# untitled.net
KiCad netlist of a schematic drawn in EAGLE
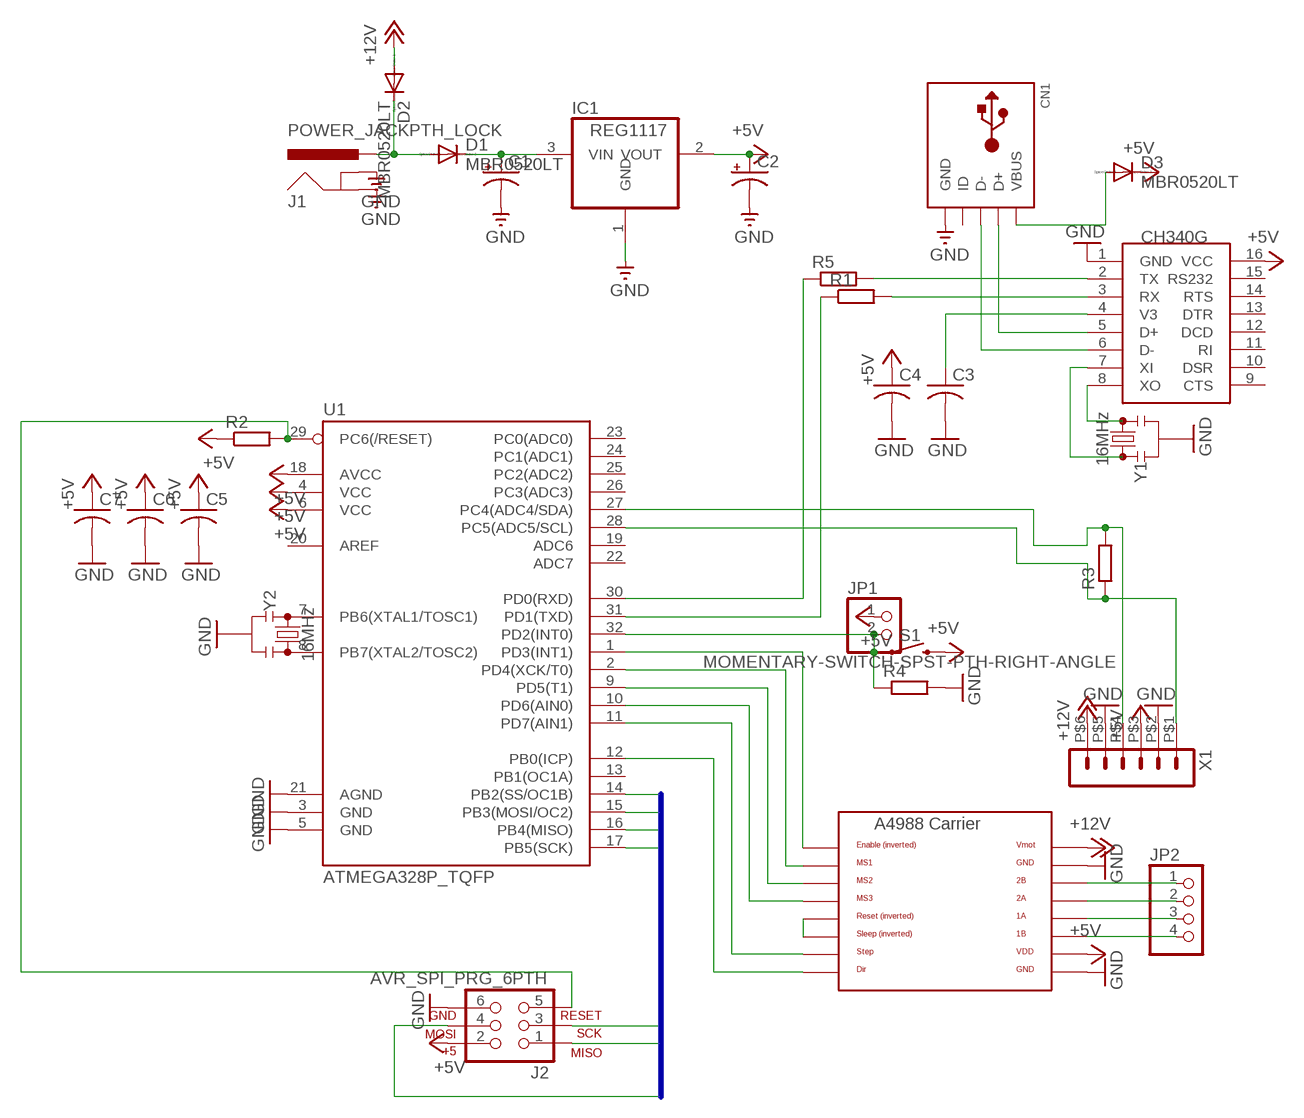
[diagram p0: schematic, sheet 1]

(export (version "E")
  (design (tool "Eeschema 10.0.6"))
  (components
    (comp (ref "C1")
      (value "CPOL-US153CLV-0405")
      (footprint "eagle-import:153CLV-0405")
      (libsource (lib "eagle-import") (part "CPOL-US153CLV-0405"))
    )
    (comp (ref "C2")
      (value "CPOL-US153CLV-0405")
      (footprint "eagle-import:153CLV-0405")
      (libsource (lib "eagle-import") (part "CPOL-US153CLV-0405"))
    )
    (comp (ref "C3")
      (value "C-USC1210")
      (footprint "eagle-import:C1210")
      (libsource (lib "eagle-import") (part "C-USC1210"))
    )
    (comp (ref "C4")
      (value "C-USC1210")
      (footprint "eagle-import:C1210")
      (libsource (lib "eagle-import") (part "C-USC1210"))
    )
    (comp (ref "C5")
      (value "C-USC1210")
      (footprint "eagle-import:C1210")
      (libsource (lib "eagle-import") (part "C-USC1210"))
    )
    (comp (ref "C6")
      (value "C-USC1210")
      (footprint "eagle-import:C1210")
      (libsource (lib "eagle-import") (part "C-USC1210"))
    )
    (comp (ref "C7")
      (value "C-USC1210")
      (footprint "eagle-import:C1210")
      (libsource (lib "eagle-import") (part "C-USC1210"))
    )
    (comp (ref "CN1")
      (value "USBMINIB")
      (footprint "eagle-import:USB-MINIB")
      (libsource (lib "eagle-import") (part "USBMINIB"))
    )
    (comp (ref "D1")
      (value "MBR0520LT")
      (footprint "eagle-import:SOD123")
      (libsource (lib "eagle-import") (part "MBR0520LT"))
    )
    (comp (ref "D2")
      (value "MBR0520LT")
      (footprint "eagle-import:SOD123")
      (libsource (lib "eagle-import") (part "MBR0520LT"))
    )
    (comp (ref "D3")
      (value "MBR0520LT")
      (footprint "eagle-import:SOD123")
      (libsource (lib "eagle-import") (part "MBR0520LT"))
    )
    (comp (ref "IC1")
      (value "REG1117")
      (footprint "eagle-import:SOT223")
      (libsource (lib "eagle-import") (part "REG1117"))
    )
    (comp (ref "J1")
      (value "POWER_JACKPTH_LOCK")
      (footprint "eagle-import:POWER_JACK_PTH_LOCK")
      (libsource (lib "eagle-import") (part "POWER_JACKPTH_LOCK"))
    )
    (comp (ref "J2")
      (value "AVR_SPI_PRG_6PTH")
      (footprint "eagle-import:2X3")
      (libsource (lib "eagle-import") (part "AVR_SPI_PRG_6PTH"))
    )
    (comp (ref "JP1")
      (value "PINHD-1X2")
      (footprint "eagle-import:1X02")
      (libsource (lib "eagle-import") (part "PINHD-1X2"))
    )
    (comp (ref "JP2")
      (value "PINHD-1X4")
      (footprint "eagle-import:1X04")
      (libsource (lib "eagle-import") (part "PINHD-1X4"))
    )
    (comp (ref "R1")
      (value "R-EU_MELF0207W")
      (footprint "eagle-import:MINI_MELF-0207W")
      (libsource (lib "eagle-import") (part "R-EU_MELF0207W"))
    )
    (comp (ref "R2")
      (value "R-EU_MELF0207W")
      (footprint "eagle-import:MINI_MELF-0207W")
      (libsource (lib "eagle-import") (part "R-EU_MELF0207W"))
    )
    (comp (ref "R3")
      (value "R-EU_MELF0207W")
      (footprint "eagle-import:MINI_MELF-0207W")
      (libsource (lib "eagle-import") (part "R-EU_MELF0207W"))
    )
    (comp (ref "R4")
      (value "R-EU_MELF0207W")
      (footprint "eagle-import:MINI_MELF-0207W")
      (libsource (lib "eagle-import") (part "R-EU_MELF0207W"))
    )
    (comp (ref "R5")
      (value "R-EU_MELF0207W")
      (footprint "eagle-import:MINI_MELF-0207W")
      (libsource (lib "eagle-import") (part "R-EU_MELF0207W"))
    )
    (comp (ref "S1")
      (value "MOMENTARY-SWITCH-SPST-PTH-RIGHT-ANGLE")
      (footprint "eagle-import:TACTILE_SWITCH_PTH_RIGHT_ANGLE")
      (libsource (lib "eagle-import") (part "MOMENTARY-SWITCH-SPST-PTH-RIGHT-ANGLE"))
    )
    (comp (ref "U$1")
      (value "CH340G")
      (footprint "eagle-import:SOIC16")
      (libsource (lib "eagle-import") (part "CH340G"))
    )
    (comp (ref "U$2")
      (value "A4988BREAKOUT")
      (footprint "eagle-import:A4988BREAKOUT")
      (libsource (lib "eagle-import") (part "A4988BREAKOUT"))
    )
    (comp (ref "U1")
      (value "ATMEGA328P_TQFP")
      (footprint "eagle-import:TQFP32-08")
      (libsource (lib "eagle-import") (part "ATMEGA328P_TQFP"))
    )
    (comp (ref "X1")
      (value "HEADER_POS6_43045-0600")
      (footprint "eagle-import:43045-0600")
      (libsource (lib "eagle-import") (part "HEADER_POS6_?43045-0600"))
    )
    (comp (ref "Y1")
      (value "16MHz")
      (footprint "eagle-import:RESONATOR-SMD-3.2X1.3")
      (libsource (lib "eagle-import") (part "RESONATOR-16MHZSMD_3.2X1.3"))
    )
    (comp (ref "Y2")
      (value "16MHz")
      (footprint "eagle-import:RESONATOR-SMD-3.2X1.3")
      (libsource (lib "eagle-import") (part "RESONATOR-16MHZSMD_3.2X1.3"))
    )
  )
  (nets
    (net (code "1") (name "+5V") (class "Default")
      (node (ref "C2") (pin "+") (pinfunction "+_+") (pintype "passive"))
      (node (ref "C4") (pin "1") (pinfunction "1_1") (pintype "passive"))
      (node (ref "C5") (pin "1") (pinfunction "1_1") (pintype "passive"))
      (node (ref "C6") (pin "1") (pinfunction "1_1") (pintype "passive"))
      (node (ref "C7") (pin "1") (pinfunction "1_1") (pintype "passive"))
      (node (ref "D3") (pin "C") (pinfunction "C_C") (pintype "passive"))
      (node (ref "IC1") (pin "2") (pinfunction "VOUT_2") (pintype "output"))
      (node (ref "J2") (pin "2") (pinfunction "2_2") (pintype "passive"))
      (node (ref "JP1") (pin "1") (pinfunction "1_1") (pintype "passive"))
      (node (ref "R2") (pin "1") (pinfunction "1_1") (pintype "passive"))
      (node (ref "S1") (pin "2") (pinfunction "2_2") (pintype "passive"))
      (node (ref "U$1") (pin "16") (pinfunction "VCC_16") (pintype "bidirectional"))
      (node (ref "U$2") (pin "VDD") (pinfunction "VDD_VDD") (pintype "power_in"))
      (node (ref "U1") (pin "18") (pinfunction "AVCC_18") (pintype "bidirectional"))
      (node (ref "U1") (pin "4") (pinfunction "VCC_4") (pintype "bidirectional"))
      (node (ref "U1") (pin "6") (pinfunction "VCC_6") (pintype "bidirectional"))
      (node (ref "X1") (pin "P$3") (pinfunction "3_P$3") (pintype "passive"))
    )
    (net (code "2") (name "+12V") (class "Default")
      (node (ref "D2") (pin "A") (pinfunction "A_A") (pintype "passive"))
      (node (ref "U$2") (pin "VMOT") (pinfunction "VMOT_VMOT") (pintype "power_in"))
      (node (ref "X1") (pin "P$6") (pinfunction "6_P$6") (pintype "passive"))
    )
    (net (code "3") (name "/MISO") (class "Default")
      (node (ref "J2") (pin "1") (pinfunction "1_1") (pintype "passive"))
      (node (ref "U1") (pin "16") (pinfunction "PB4(MISO)_16") (pintype "bidirectional"))
    )
    (net (code "4") (name "/MOSI") (class "Default")
      (node (ref "J2") (pin "4") (pinfunction "4_4") (pintype "passive"))
      (node (ref "U1") (pin "15") (pinfunction "PB3(MOSI/OC2)_15") (pintype "bidirectional"))
    )
    (net (code "5") (name "/SCK") (class "Default")
      (node (ref "J2") (pin "3") (pinfunction "3_3") (pintype "passive"))
      (node (ref "U1") (pin "17") (pinfunction "PB5(SCK)_17") (pintype "bidirectional"))
    )
    (net (code "6") (name "GND") (class "Default")
      (node (ref "C1") (pin "-") (pinfunction "-_-") (pintype "passive"))
      (node (ref "C2") (pin "-") (pinfunction "-_-") (pintype "passive"))
      (node (ref "C3") (pin "2") (pinfunction "2_2") (pintype "passive"))
      (node (ref "C4") (pin "2") (pinfunction "2_2") (pintype "passive"))
      (node (ref "C5") (pin "2") (pinfunction "2_2") (pintype "passive"))
      (node (ref "C6") (pin "2") (pinfunction "2_2") (pintype "passive"))
      (node (ref "C7") (pin "2") (pinfunction "2_2") (pintype "passive"))
      (node (ref "CN1") (pin "GND") (pinfunction "GND_GND") (pintype "power_in"))
      (node (ref "IC1") (pin "1") (pinfunction "GND_1") (pintype "power_in"))
      (node (ref "J1") (pin "GND") (pinfunction "GND_GND") (pintype "bidirectional"))
      (node (ref "J1") (pin "GNDBREAK") (pinfunction "GNDBREAK_GNDBREAK") (pintype "bidirectional"))
      (node (ref "J2") (pin "6") (pinfunction "6_6") (pintype "passive"))
      (node (ref "R4") (pin "2") (pinfunction "2_2") (pintype "passive"))
      (node (ref "U$1") (pin "1") (pinfunction "GND_1") (pintype "bidirectional"))
      (node (ref "U$2") (pin "GND") (pinfunction "GND_GND") (pintype "power_in"))
      (node (ref "U$2") (pin "GND@0") (pinfunction "GND_GND@0") (pintype "power_in"))
      (node (ref "U1") (pin "21") (pinfunction "AGND_21") (pintype "bidirectional"))
      (node (ref "U1") (pin "3") (pinfunction "GND_3") (pintype "bidirectional"))
      (node (ref "U1") (pin "5") (pinfunction "GND_5") (pintype "bidirectional"))
      (node (ref "X1") (pin "P$2") (pinfunction "2_P$2") (pintype "passive"))
      (node (ref "X1") (pin "P$5") (pinfunction "5_P$5") (pintype "passive"))
      (node (ref "Y1") (pin "2") (pinfunction "2_2") (pintype "passive"))
      (node (ref "Y2") (pin "2") (pinfunction "2_2") (pintype "passive"))
    )
    (net (code "7") (name "Net-(CN1-PadVBUS)") (class "Default")
      (node (ref "CN1") (pin "VBUS") (pinfunction "VBUS_VBUS") (pintype "power_in"))
      (node (ref "D3") (pin "A") (pinfunction "A_A") (pintype "passive"))
    )
    (net (code "8") (name "Net-(D1-PadA)") (class "Default")
      (node (ref "D1") (pin "A") (pinfunction "A_A") (pintype "passive"))
      (node (ref "D2") (pin "C") (pinfunction "C_C") (pintype "passive"))
      (node (ref "J1") (pin "PWR") (pinfunction "PWR_PWR") (pintype "bidirectional"))
    )
    (net (code "9") (name "Net-(IC1-VIN)") (class "Default")
      (node (ref "C1") (pin "+") (pinfunction "+_+") (pintype "passive"))
      (node (ref "D1") (pin "C") (pinfunction "C_C") (pintype "passive"))
      (node (ref "IC1") (pin "3") (pinfunction "VIN_3") (pintype "input"))
    )
    (net (code "10") (name "Net-(JP2-Pad1)") (class "Default")
      (node (ref "JP2") (pin "1") (pinfunction "1_1") (pintype "passive"))
      (node (ref "U$2") (pin "2B") (pinfunction "2B_2B") (pintype "output"))
    )
    (net (code "11") (name "Net-(JP2-Pad2)") (class "Default")
      (node (ref "JP2") (pin "2") (pinfunction "2_2") (pintype "passive"))
      (node (ref "U$2") (pin "2A") (pinfunction "2A_2A") (pintype "output"))
    )
    (net (code "12") (name "Net-(JP2-Pad3)") (class "Default")
      (node (ref "JP2") (pin "3") (pinfunction "3_3") (pintype "passive"))
      (node (ref "U$2") (pin "1A") (pinfunction "1A_1A") (pintype "output"))
    )
    (net (code "13") (name "Net-(JP2-Pad4)") (class "Default")
      (node (ref "JP2") (pin "4") (pinfunction "4_4") (pintype "passive"))
      (node (ref "U$2") (pin "1B") (pinfunction "1B_1B") (pintype "output"))
    )
    (net (code "14") (name "Net-(U$1-D+)") (class "Default")
      (node (ref "CN1") (pin "D+") (pinfunction "D+_D+") (pintype "bidirectional"))
      (node (ref "U$1") (pin "5") (pinfunction "D+_5") (pintype "bidirectional"))
    )
    (net (code "15") (name "Net-(U$1-D-)") (class "Default")
      (node (ref "CN1") (pin "D-") (pinfunction "D-_D-") (pintype "bidirectional"))
      (node (ref "U$1") (pin "6") (pinfunction "D-_6") (pintype "bidirectional"))
    )
    (net (code "16") (name "Net-(U$1-RX)") (class "Default")
      (node (ref "R1") (pin "2") (pinfunction "2_2") (pintype "passive"))
      (node (ref "U$1") (pin "3") (pinfunction "RX_3") (pintype "bidirectional"))
    )
    (net (code "17") (name "Net-(U$1-TX)") (class "Default")
      (node (ref "R5") (pin "2") (pinfunction "2_2") (pintype "passive"))
      (node (ref "U$1") (pin "2") (pinfunction "TX_2") (pintype "bidirectional"))
    )
    (net (code "18") (name "Net-(U$1-V3)") (class "Default")
      (node (ref "C3") (pin "1") (pinfunction "1_1") (pintype "passive"))
      (node (ref "U$1") (pin "4") (pinfunction "V3_4") (pintype "bidirectional"))
    )
    (net (code "19") (name "Net-(U$1-XI)") (class "Default")
      (node (ref "U$1") (pin "7") (pinfunction "XI_7") (pintype "bidirectional"))
      (node (ref "Y1") (pin "1") (pinfunction "1_1") (pintype "passive"))
    )
    (net (code "20") (name "Net-(U$1-XO)") (class "Default")
      (node (ref "U$1") (pin "8") (pinfunction "XO_8") (pintype "bidirectional"))
      (node (ref "Y1") (pin "3") (pinfunction "3_3") (pintype "passive"))
    )
    (net (code "21") (name "Net-(U$2-SLEEP)") (class "Default")
      (node (ref "U$2") (pin "RST") (pinfunction "RST_RST") (pintype "input"))
      (node (ref "U$2") (pin "SLP") (pinfunction "SLEEP_SLP") (pintype "input"))
    )
    (net (code "22") (name "Net-(U1-PB0(ICP))") (class "Default")
      (node (ref "U$2") (pin "DIR") (pinfunction "DIR_DIR") (pintype "input"))
      (node (ref "U1") (pin "12") (pinfunction "PB0(ICP)_12") (pintype "bidirectional"))
    )
    (net (code "23") (name "Net-(U1-PB6(XTAL1{slash}TOSC1))") (class "Default")
      (node (ref "U1") (pin "7") (pinfunction "PB6(XTAL1/TOSC1)_7") (pintype "bidirectional"))
      (node (ref "Y2") (pin "1") (pinfunction "1_1") (pintype "passive"))
    )
    (net (code "24") (name "Net-(U1-PB7(XTAL2{slash}TOSC2))") (class "Default")
      (node (ref "U1") (pin "8") (pinfunction "PB7(XTAL2/TOSC2)_8") (pintype "bidirectional"))
      (node (ref "Y2") (pin "3") (pinfunction "3_3") (pintype "passive"))
    )
    (net (code "25") (name "Net-(U1-PC4(ADC4{slash}SDA))") (class "Default")
      (node (ref "R3") (pin "2") (pinfunction "2_2") (pintype "passive"))
      (node (ref "U1") (pin "27") (pinfunction "PC4(ADC4/SDA)_27") (pintype "bidirectional"))
      (node (ref "X1") (pin "P$4") (pinfunction "4_P$4") (pintype "passive"))
    )
    (net (code "26") (name "Net-(U1-PC5(ADC5{slash}SCL))") (class "Default")
      (node (ref "R3") (pin "1") (pinfunction "1_1") (pintype "passive"))
      (node (ref "U1") (pin "28") (pinfunction "PC5(ADC5/SCL)_28") (pintype "bidirectional"))
      (node (ref "X1") (pin "P$1") (pinfunction "1_P$1") (pintype "passive"))
    )
    (net (code "27") (name "Net-(U1-PC6({slash}RESET))") (class "Default")
      (node (ref "J2") (pin "5") (pinfunction "5_5") (pintype "passive"))
      (node (ref "R2") (pin "2") (pinfunction "2_2") (pintype "passive"))
      (node (ref "U1") (pin "29") (pinfunction "PC6(/RESET)_29") (pintype "bidirectional"))
    )
    (net (code "28") (name "Net-(U1-PD0(RXD))") (class "Default")
      (node (ref "R5") (pin "1") (pinfunction "1_1") (pintype "passive"))
      (node (ref "U1") (pin "30") (pinfunction "PD0(RXD)_30") (pintype "bidirectional"))
    )
    (net (code "29") (name "Net-(U1-PD1(TXD))") (class "Default")
      (node (ref "R1") (pin "1") (pinfunction "1_1") (pintype "passive"))
      (node (ref "U1") (pin "31") (pinfunction "PD1(TXD)_31") (pintype "bidirectional"))
    )
    (net (code "30") (name "Net-(U1-PD2(INT0))") (class "Default")
      (node (ref "JP1") (pin "2") (pinfunction "2_2") (pintype "passive"))
      (node (ref "R4") (pin "1") (pinfunction "1_1") (pintype "passive"))
      (node (ref "S1") (pin "1") (pinfunction "1_1") (pintype "passive"))
      (node (ref "U1") (pin "32") (pinfunction "PD2(INT0)_32") (pintype "bidirectional"))
    )
    (net (code "31") (name "Net-(U1-PD3(INT1))") (class "Default")
      (node (ref "U$2") (pin "EN") (pinfunction "EN_EN") (pintype "input"))
      (node (ref "U1") (pin "1") (pinfunction "PD3(INT1)_1") (pintype "bidirectional"))
    )
    (net (code "32") (name "Net-(U1-PD4(XCK{slash}T0))") (class "Default")
      (node (ref "U$2") (pin "MS1") (pinfunction "MS1_MS1") (pintype "input"))
      (node (ref "U1") (pin "2") (pinfunction "PD4(XCK/T0)_2") (pintype "bidirectional"))
    )
    (net (code "33") (name "Net-(U1-PD5(T1))") (class "Default")
      (node (ref "U$2") (pin "MS2") (pinfunction "MS2_MS2") (pintype "input"))
      (node (ref "U1") (pin "9") (pinfunction "PD5(T1)_9") (pintype "bidirectional"))
    )
    (net (code "34") (name "Net-(U1-PD6(AIN0))") (class "Default")
      (node (ref "U$2") (pin "MS3") (pinfunction "MS3_MS3") (pintype "input"))
      (node (ref "U1") (pin "10") (pinfunction "PD6(AIN0)_10") (pintype "bidirectional"))
    )
    (net (code "35") (name "Net-(U1-PD7(AIN1))") (class "Default")
      (node (ref "U$2") (pin "STEP") (pinfunction "STEP_STEP") (pintype "input"))
      (node (ref "U1") (pin "11") (pinfunction "PD7(AIN1)_11") (pintype "bidirectional"))
    )
    (net (code "36") (name "unconnected-(CN1-PadID)") (class "Default")
      (node (ref "CN1") (pin "ID") (pinfunction "ID_ID") (pintype "bidirectional"))
    )
    (net (code "37") (name "unconnected-(U$1-CTS-Pad9)") (class "Default")
      (node (ref "U$1") (pin "9") (pinfunction "CTS_9") (pintype "bidirectional"))
    )
    (net (code "38") (name "unconnected-(U$1-DCD-Pad12)") (class "Default")
      (node (ref "U$1") (pin "12") (pinfunction "DCD_12") (pintype "bidirectional"))
    )
    (net (code "39") (name "unconnected-(U$1-DSR-Pad10)") (class "Default")
      (node (ref "U$1") (pin "10") (pinfunction "DSR_10") (pintype "bidirectional"))
    )
    (net (code "40") (name "unconnected-(U$1-DTR-Pad13)") (class "Default")
      (node (ref "U$1") (pin "13") (pinfunction "DTR_13") (pintype "bidirectional"))
    )
    (net (code "41") (name "unconnected-(U$1-RI-Pad11)") (class "Default")
      (node (ref "U$1") (pin "11") (pinfunction "RI_11") (pintype "bidirectional"))
    )
    (net (code "42") (name "unconnected-(U$1-RS232-Pad15)") (class "Default")
      (node (ref "U$1") (pin "15") (pinfunction "RS232_15") (pintype "bidirectional"))
    )
    (net (code "43") (name "unconnected-(U$1-RTS-Pad14)") (class "Default")
      (node (ref "U$1") (pin "14") (pinfunction "RTS_14") (pintype "bidirectional"))
    )
    (net (code "44") (name "unconnected-(U1-ADC6-Pad19)") (class "Default")
      (node (ref "U1") (pin "19") (pinfunction "ADC6_19") (pintype "bidirectional"))
    )
    (net (code "45") (name "unconnected-(U1-ADC7-Pad22)") (class "Default")
      (node (ref "U1") (pin "22") (pinfunction "ADC7_22") (pintype "bidirectional"))
    )
    (net (code "46") (name "unconnected-(U1-AREF-Pad20)") (class "Default")
      (node (ref "U1") (pin "20") (pinfunction "AREF_20") (pintype "bidirectional"))
    )
    (net (code "47") (name "unconnected-(U1-PB1(OC1A)-Pad13)") (class "Default")
      (node (ref "U1") (pin "13") (pinfunction "PB1(OC1A)_13") (pintype "bidirectional"))
    )
    (net (code "48") (name "unconnected-(U1-PB2(SS{slash}OC1B)-Pad14)") (class "Default")
      (node (ref "U1") (pin "14") (pinfunction "PB2(SS/OC1B)_14") (pintype "bidirectional"))
    )
    (net (code "49") (name "unconnected-(U1-PC0(ADC0)-Pad23)") (class "Default")
      (node (ref "U1") (pin "23") (pinfunction "PC0(ADC0)_23") (pintype "bidirectional"))
    )
    (net (code "50") (name "unconnected-(U1-PC1(ADC1)-Pad24)") (class "Default")
      (node (ref "U1") (pin "24") (pinfunction "PC1(ADC1)_24") (pintype "bidirectional"))
    )
    (net (code "51") (name "unconnected-(U1-PC2(ADC2)-Pad25)") (class "Default")
      (node (ref "U1") (pin "25") (pinfunction "PC2(ADC2)_25") (pintype "bidirectional"))
    )
    (net (code "52") (name "unconnected-(U1-PC3(ADC3)-Pad26)") (class "Default")
      (node (ref "U1") (pin "26") (pinfunction "PC3(ADC3)_26") (pintype "bidirectional"))
    )
  )
)
